# science_controller.net
KiCad netlist of a schematic drawn in EAGLE
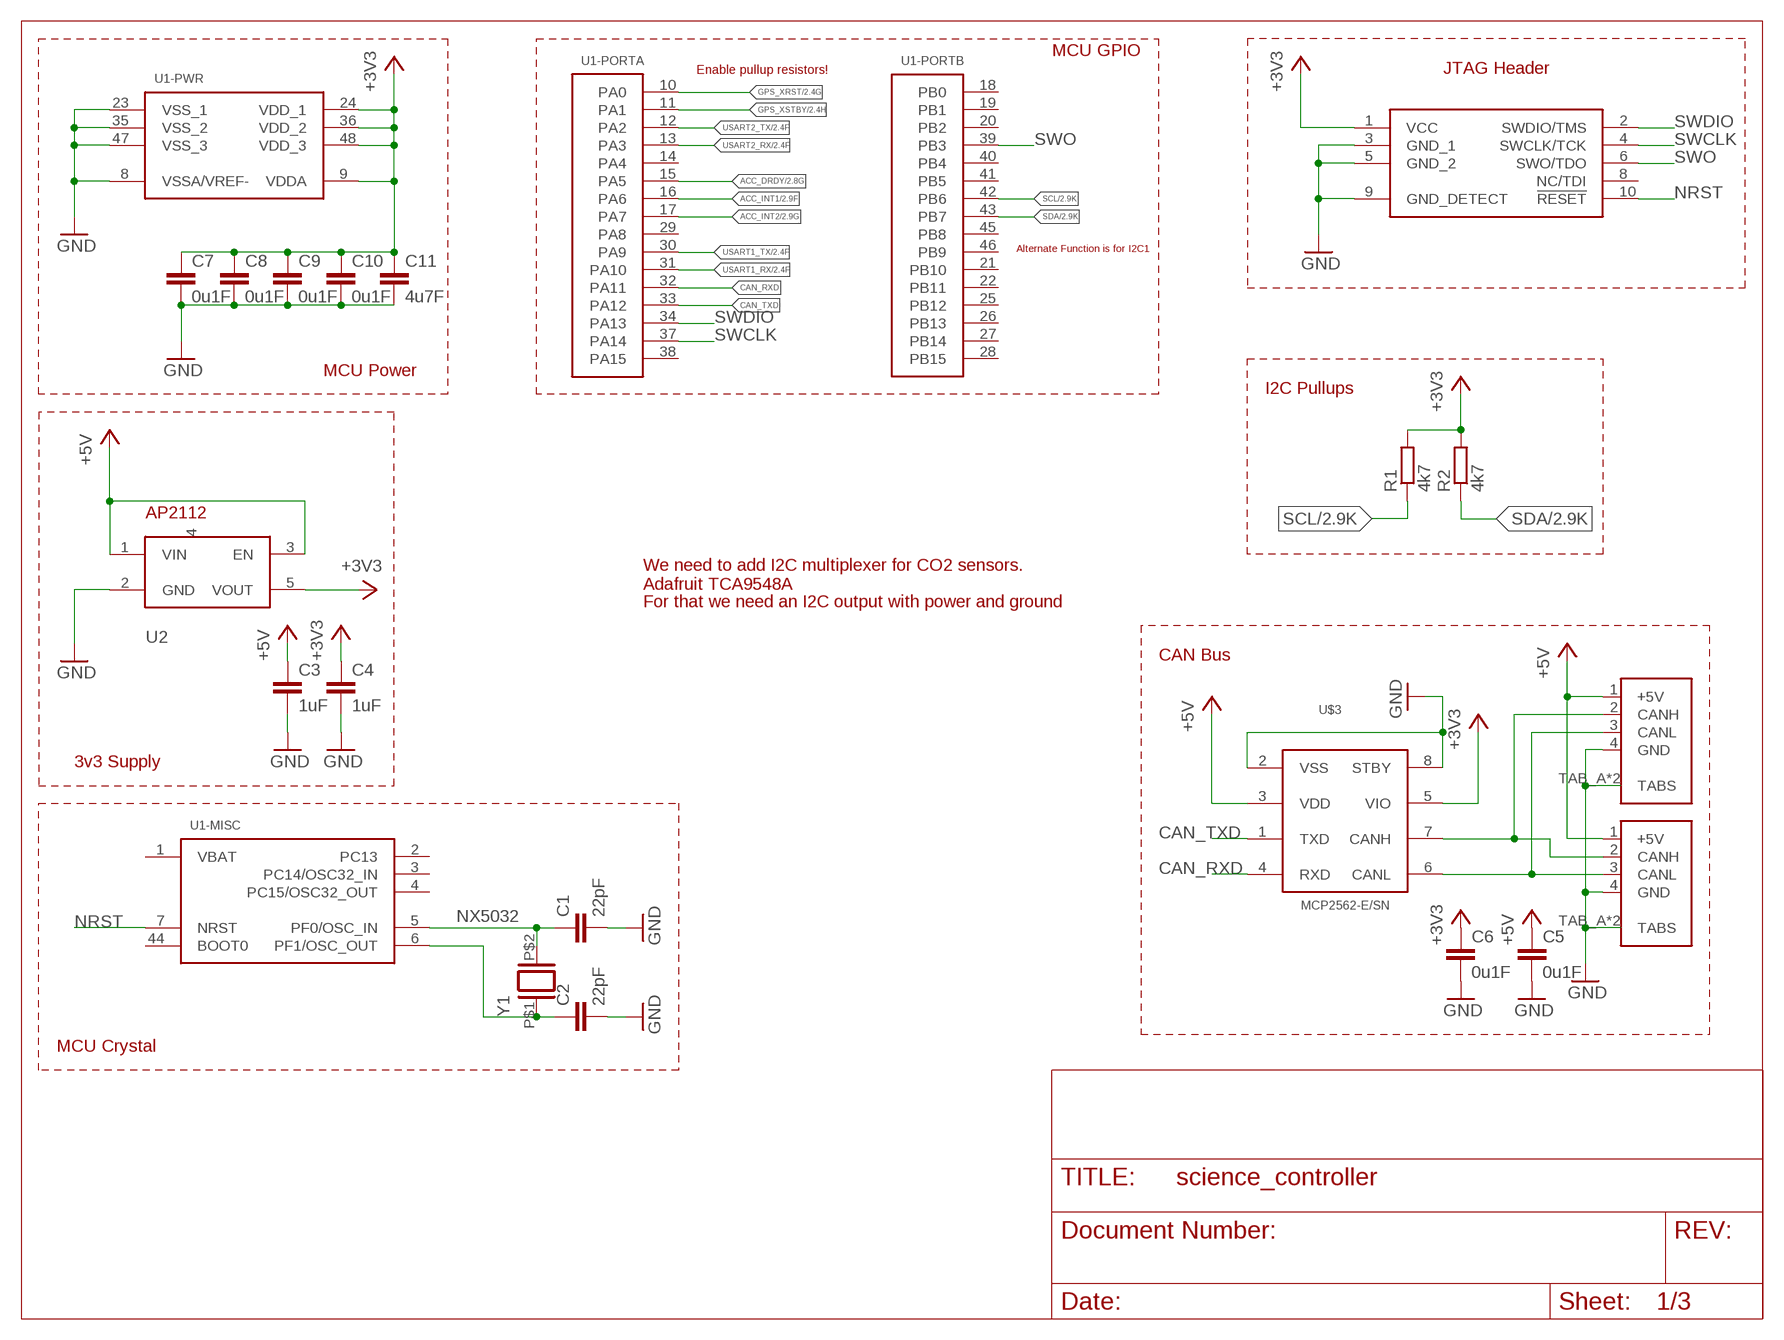
[diagram p0: schematic, sheet 1]
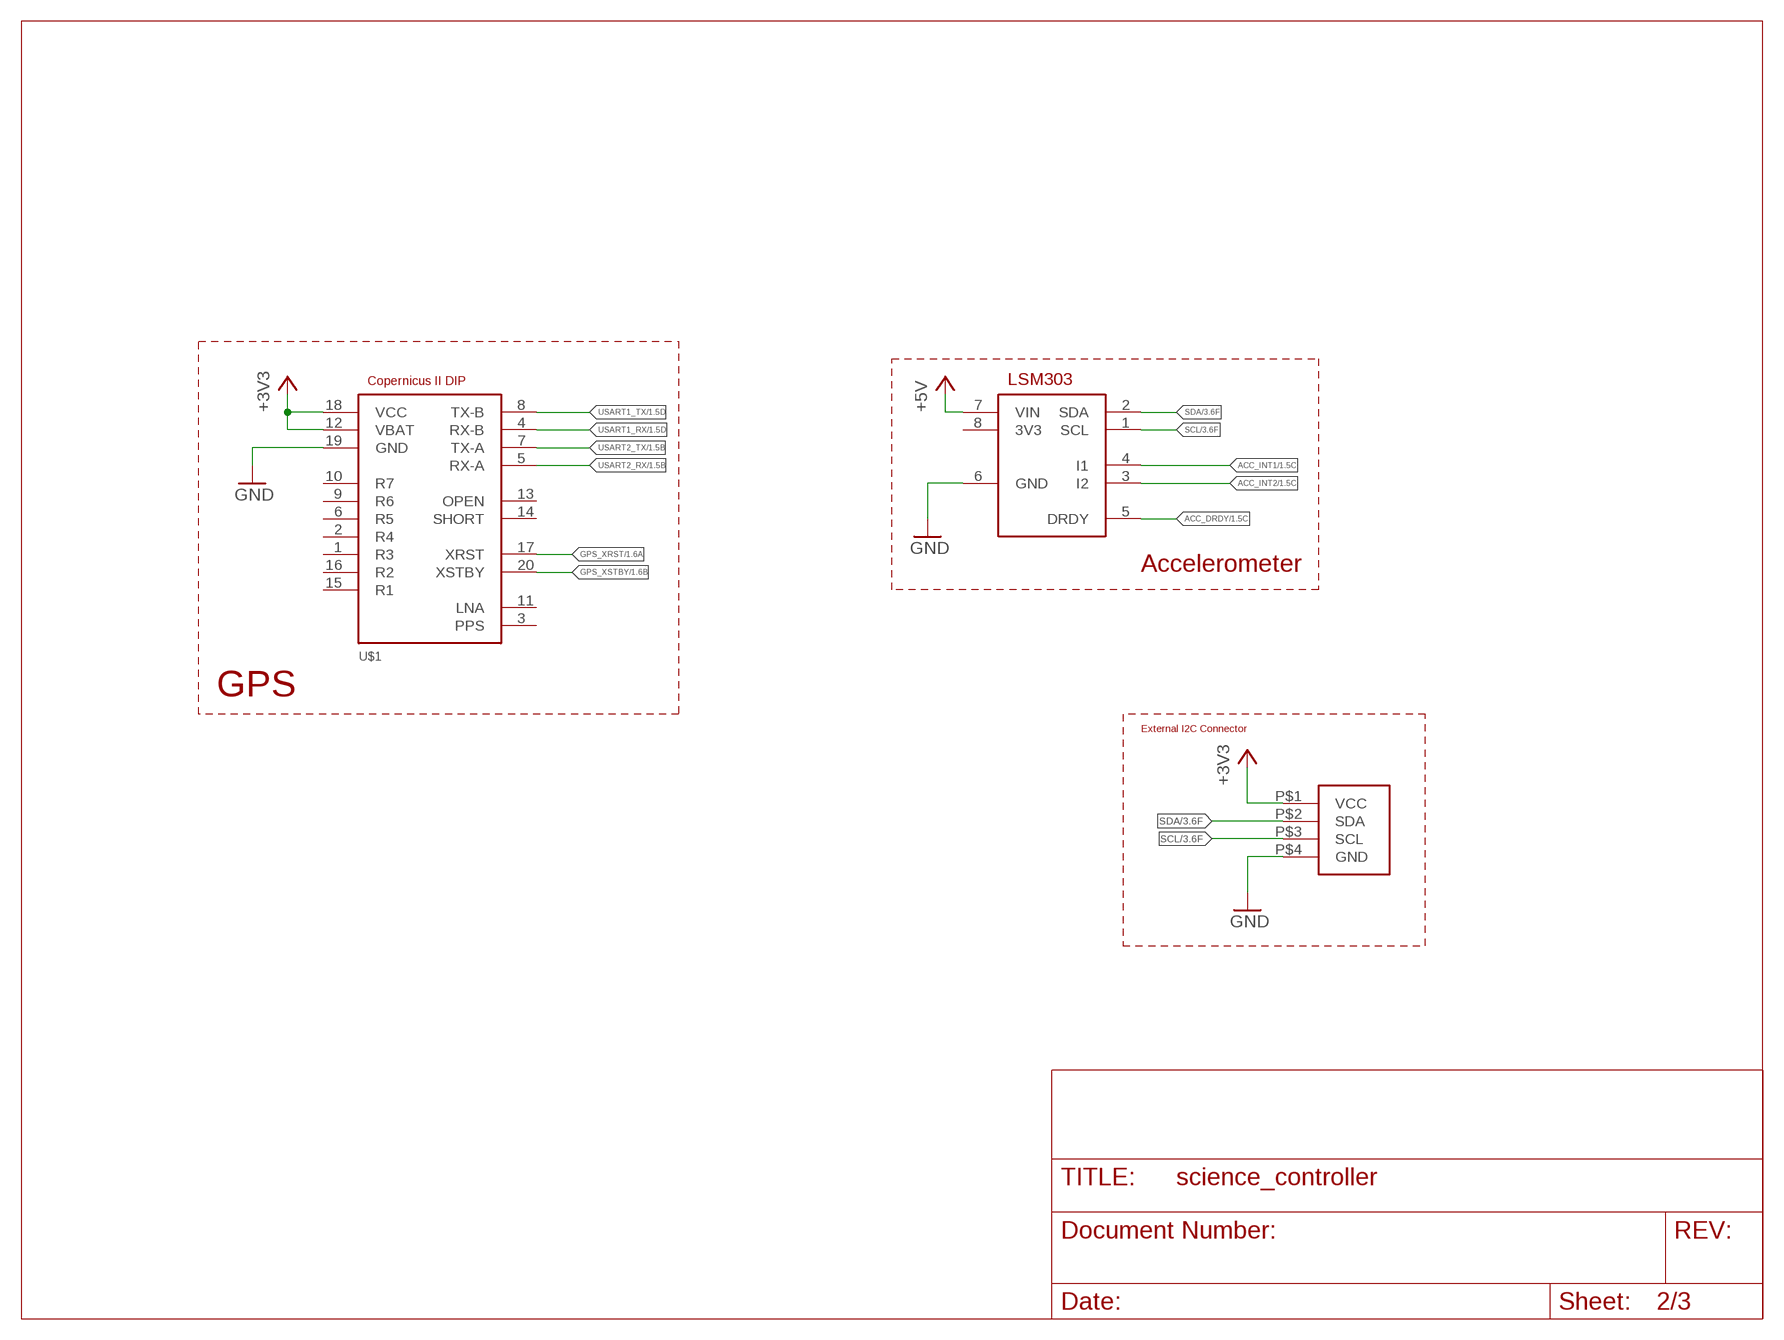
[diagram p1: schematic, sheet 2]
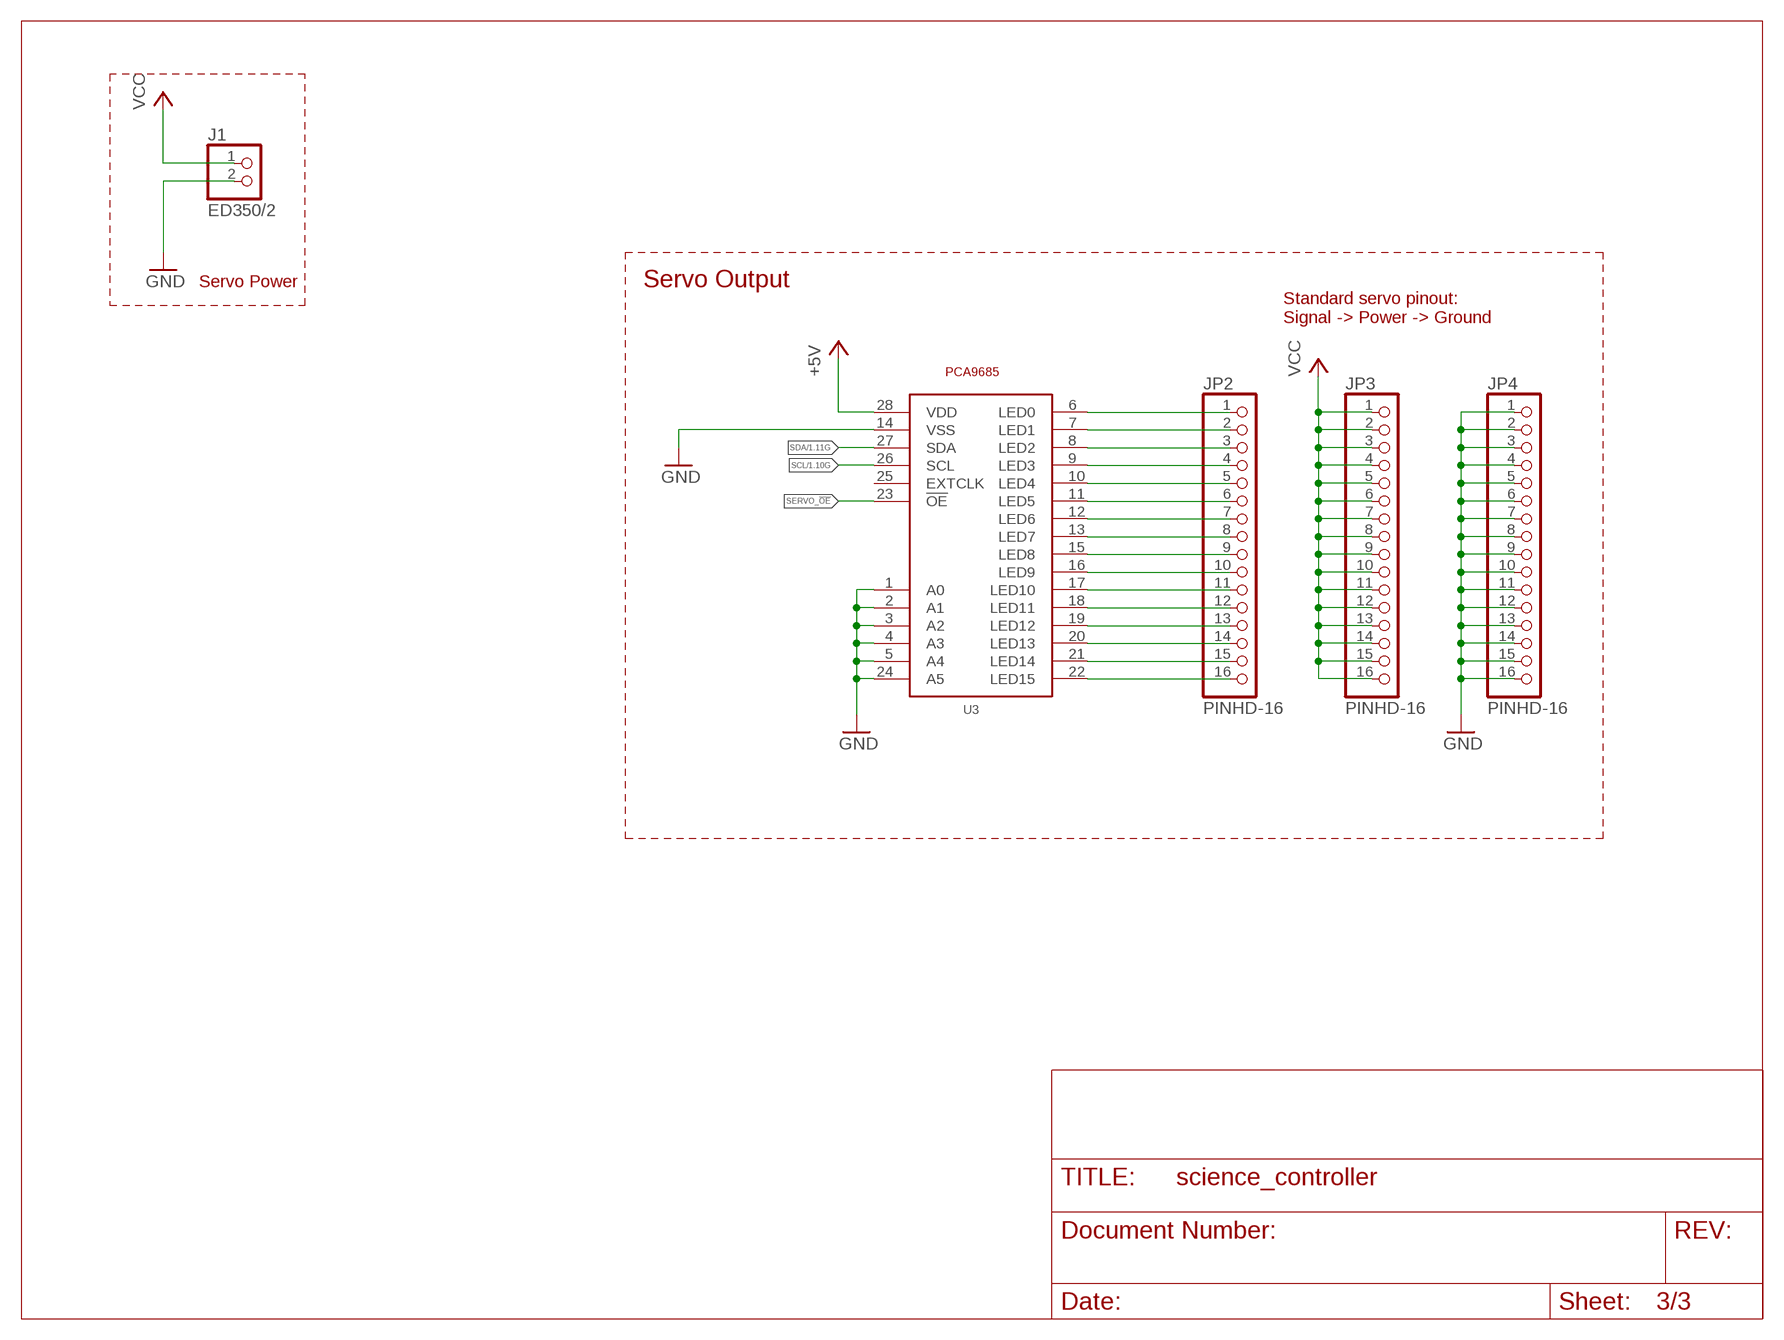
[diagram p2: schematic, sheet 3]

(export (version "E")
  (design (tool "Eeschema 10.0.6"))
  (components
    (comp (ref "C1")
      (value "22pF")
      (footprint "eagle-import:C0805")
      (libsource (lib "eagle-import") (part "C-EUC0805"))
    )
    (comp (ref "C2")
      (value "22pF")
      (footprint "eagle-import:C0805")
      (libsource (lib "eagle-import") (part "C-EUC0805"))
    )
    (comp (ref "C3")
      (value "1uF")
      (footprint "eagle-import:C0805")
      (libsource (lib "eagle-import") (part "C-EUC0805"))
    )
    (comp (ref "C4")
      (value "1uF")
      (footprint "eagle-import:C0805")
      (libsource (lib "eagle-import") (part "C-EUC0805"))
    )
    (comp (ref "C5")
      (value "0u1F")
      (footprint "eagle-import:C0805")
      (libsource (lib "eagle-import") (part "C-EUC0805"))
    )
    (comp (ref "C6")
      (value "0u1F")
      (footprint "eagle-import:C0805")
      (libsource (lib "eagle-import") (part "C-EUC0805"))
    )
    (comp (ref "C7")
      (value "0u1F")
      (footprint "eagle-import:C0805")
      (libsource (lib "eagle-import") (part "C-EUC0805"))
    )
    (comp (ref "C8")
      (value "0u1F")
      (footprint "eagle-import:C0805")
      (libsource (lib "eagle-import") (part "C-EUC0805"))
    )
    (comp (ref "C9")
      (value "0u1F")
      (footprint "eagle-import:C0805")
      (libsource (lib "eagle-import") (part "C-EUC0805"))
    )
    (comp (ref "C10")
      (value "0u1F")
      (footprint "eagle-import:C0805")
      (libsource (lib "eagle-import") (part "C-EUC0805"))
    )
    (comp (ref "C11")
      (value "4u7F")
      (footprint "eagle-import:C0805")
      (libsource (lib "eagle-import") (part "C-EUC0805"))
    )
    (comp (ref "CON1")
      (value "UAVCAN_MICRO")
      (footprint "eagle-import:SM04B-GHS-TB")
      (libsource (lib "eagle-import") (part "UAVCAN_MICRO"))
    )
    (comp (ref "CON2")
      (value "UAVCAN_MICRO")
      (footprint "eagle-import:SM04B-GHS-TB")
      (libsource (lib "eagle-import") (part "UAVCAN_MICRO"))
    )
    (comp (ref "JP1")
      (value "CORTEX-M-DBG")
      (footprint "eagle-import:FTSH-105-01-F-DV-007")
      (libsource (lib "eagle-import") (part "CORTEX-M-DBG"))
    )
    (comp (ref "R1")
      (value "4k7")
      (footprint "eagle-import:R0805")
      (libsource (lib "eagle-import") (part "R-EU_R0805"))
    )
    (comp (ref "R2")
      (value "4k7")
      (footprint "eagle-import:R0805")
      (libsource (lib "eagle-import") (part "R-EU_R0805"))
    )
    (comp (ref "U$3")
      (value "MCP2562-E/SN")
      (footprint "eagle-import:SOIC8")
      (libsource (lib "eagle-import") (part "MCP2562-E/SN"))
    )
    (comp (ref "U1")
      (value "STM32F303CB")
      (footprint "eagle-import:LQFP48")
      (libsource (lib "eagle-import") (part "STM32F303CB"))
    )
    (comp (ref "U2")
      (value "AP2112K-3.3TRG1")
      (footprint "eagle-import:SOT25")
      (libsource (lib "eagle-import") (part "AP2112K-3.3TRG1"))
    )
    (comp (ref "Y1")
      (value "NX5032")
      (footprint "eagle-import:NX5032")
      (libsource (lib "eagle-import") (part "NX5032"))
    )
    (comp (ref "J1")
      (value "ED350/2")
      (footprint "eagle-import:ED350_2")
      (libsource (lib "eagle-import") (part "ED350/2"))
    )
    (comp (ref "JP2")
      (value "PINHD-16")
      (footprint "eagle-import:1X16")
      (libsource (lib "eagle-import") (part "PINHD-16"))
    )
    (comp (ref "JP3")
      (value "PINHD-16")
      (footprint "eagle-import:1X16")
      (libsource (lib "eagle-import") (part "PINHD-16"))
    )
    (comp (ref "JP4")
      (value "PINHD-16")
      (footprint "eagle-import:1X16")
      (libsource (lib "eagle-import") (part "PINHD-16"))
    )
    (comp (ref "U3")
      (value "PCA9685PW")
      (footprint "eagle-import:TSSOP28")
      (libsource (lib "eagle-import") (part "PCA9685PW"))
    )
    (comp (ref "P1")
      (value "I2C-PWR")
      (footprint "eagle-import:TE_5-103669-3")
      (libsource (lib "eagle-import") (part "I2C-PWR"))
    )
    (comp (ref "U$1")
      (value "COPERN2-DIP")
      (footprint "eagle-import:COPERN2-DIP")
      (libsource (lib "eagle-import") (part "COPERN2-DIP"))
    )
    (comp (ref "U$2")
      (value "LSM303-BRKOUT")
      (footprint "eagle-import:1X08")
      (libsource (lib "eagle-import") (part "LSM303-BRKOUT"))
    )
  )
  (nets
    (net (code "1") (name "+3V3") (class "Default")
      (node (ref "C10") (pin "1") (pinfunction "1_1") (pintype "passive"))
      (node (ref "C11") (pin "1") (pinfunction "1_1") (pintype "passive"))
      (node (ref "C4") (pin "1") (pinfunction "1_1") (pintype "passive"))
      (node (ref "C6") (pin "1") (pinfunction "1_1") (pintype "passive"))
      (node (ref "C7") (pin "1") (pinfunction "1_1") (pintype "passive"))
      (node (ref "C8") (pin "1") (pinfunction "1_1") (pintype "passive"))
      (node (ref "C9") (pin "1") (pinfunction "1_1") (pintype "passive"))
      (node (ref "JP1") (pin "1") (pinfunction "VCC_1") (pintype "bidirectional"))
      (node (ref "P1") (pin "P$1") (pinfunction "VCC_P$1") (pintype "bidirectional"))
      (node (ref "R1") (pin "2") (pinfunction "2_2") (pintype "passive"))
      (node (ref "R2") (pin "2") (pinfunction "2_2") (pintype "passive"))
      (node (ref "U$1") (pin "12") (pinfunction "VBAT_12") (pintype "bidirectional"))
      (node (ref "U$1") (pin "18") (pinfunction "VCC_18") (pintype "bidirectional"))
      (node (ref "U$3") (pin "5") (pinfunction "VIO_5") (pintype "bidirectional"))
      (node (ref "U1") (pin "24") (pinfunction "VDD_1_24") (pintype "bidirectional"))
      (node (ref "U1") (pin "36") (pinfunction "VDD_2_36") (pintype "bidirectional"))
      (node (ref "U1") (pin "48") (pinfunction "VDD_3_48") (pintype "bidirectional"))
      (node (ref "U1") (pin "9") (pinfunction "VDDA_9") (pintype "bidirectional"))
      (node (ref "U2") (pin "5") (pinfunction "VOUT_5") (pintype "bidirectional"))
    )
    (net (code "2") (name "+5V") (class "Default")
      (node (ref "C3") (pin "1") (pinfunction "1_1") (pintype "passive"))
      (node (ref "C5") (pin "1") (pinfunction "1_1") (pintype "passive"))
      (node (ref "CON1") (pin "1") (pinfunction "+5V_1") (pintype "bidirectional"))
      (node (ref "CON2") (pin "1") (pinfunction "+5V_1") (pintype "bidirectional"))
      (node (ref "U$2") (pin "7") (pinfunction "VIN_7") (pintype "bidirectional"))
      (node (ref "U$3") (pin "3") (pinfunction "VDD_3") (pintype "bidirectional"))
      (node (ref "U2") (pin "1") (pinfunction "VIN_1") (pintype "bidirectional"))
      (node (ref "U2") (pin "3") (pinfunction "EN_3") (pintype "bidirectional"))
      (node (ref "U3") (pin "28") (pinfunction "VDD_28") (pintype "bidirectional"))
    )
    (net (code "3") (name "ACC_DRDY") (class "Default")
      (node (ref "U$2") (pin "5") (pinfunction "DRDY_5") (pintype "bidirectional"))
      (node (ref "U1") (pin "15") (pinfunction "PA5_15") (pintype "bidirectional"))
    )
    (net (code "4") (name "ACC_INT1") (class "Default")
      (node (ref "U$2") (pin "4") (pinfunction "I1_4") (pintype "bidirectional"))
      (node (ref "U1") (pin "16") (pinfunction "PA6_16") (pintype "bidirectional"))
    )
    (net (code "5") (name "ACC_INT2") (class "Default")
      (node (ref "U$2") (pin "3") (pinfunction "I2_3") (pintype "bidirectional"))
      (node (ref "U1") (pin "17") (pinfunction "PA7_17") (pintype "bidirectional"))
    )
    (net (code "6") (name "CAN_RXD") (class "Default")
      (node (ref "U$3") (pin "4") (pinfunction "RXD_4") (pintype "bidirectional"))
      (node (ref "U1") (pin "32") (pinfunction "PA11_32") (pintype "bidirectional"))
    )
    (net (code "7") (name "CAN_TXD") (class "Default")
      (node (ref "U$3") (pin "1") (pinfunction "TXD_1") (pintype "bidirectional"))
      (node (ref "U1") (pin "33") (pinfunction "PA12_33") (pintype "bidirectional"))
    )
    (net (code "8") (name "GND") (class "Default")
      (node (ref "C1") (pin "2") (pinfunction "2_2") (pintype "passive"))
      (node (ref "C10") (pin "2") (pinfunction "2_2") (pintype "passive"))
      (node (ref "C11") (pin "2") (pinfunction "2_2") (pintype "passive"))
      (node (ref "C2") (pin "2") (pinfunction "2_2") (pintype "passive"))
      (node (ref "C3") (pin "2") (pinfunction "2_2") (pintype "passive"))
      (node (ref "C4") (pin "2") (pinfunction "2_2") (pintype "passive"))
      (node (ref "C5") (pin "2") (pinfunction "2_2") (pintype "passive"))
      (node (ref "C6") (pin "2") (pinfunction "2_2") (pintype "passive"))
      (node (ref "C7") (pin "2") (pinfunction "2_2") (pintype "passive"))
      (node (ref "C8") (pin "2") (pinfunction "2_2") (pintype "passive"))
      (node (ref "C9") (pin "2") (pinfunction "2_2") (pintype "passive"))
      (node (ref "CON1") (pin "4") (pinfunction "GND_4") (pintype "bidirectional"))
      (node (ref "CON1") (pin "TAB_A") (pinfunction "TABS_TAB_A") (pintype "bidirectional"))
      (node (ref "CON1") (pin "TAB_B") (pinfunction "TABS_TAB_B") (pintype "bidirectional"))
      (node (ref "CON2") (pin "4") (pinfunction "GND_4") (pintype "bidirectional"))
      (node (ref "CON2") (pin "TAB_A") (pinfunction "TABS_TAB_A") (pintype "bidirectional"))
      (node (ref "CON2") (pin "TAB_B") (pinfunction "TABS_TAB_B") (pintype "bidirectional"))
      (node (ref "J1") (pin "2") (pinfunction "2_2") (pintype "passive"))
      (node (ref "JP1") (pin "3") (pinfunction "GND_1_3") (pintype "bidirectional"))
      (node (ref "JP1") (pin "5") (pinfunction "GND_2_5") (pintype "bidirectional"))
      (node (ref "JP1") (pin "9") (pinfunction "GND_DETECT_9") (pintype "bidirectional"))
      (node (ref "JP4") (pin "1") (pinfunction "1_1") (pintype "passive"))
      (node (ref "JP4") (pin "10") (pinfunction "10_10") (pintype "passive"))
      (node (ref "JP4") (pin "11") (pinfunction "11_11") (pintype "passive"))
      (node (ref "JP4") (pin "12") (pinfunction "12_12") (pintype "passive"))
      (node (ref "JP4") (pin "13") (pinfunction "13_13") (pintype "passive"))
      (node (ref "JP4") (pin "14") (pinfunction "14_14") (pintype "passive"))
      (node (ref "JP4") (pin "15") (pinfunction "15_15") (pintype "passive"))
      (node (ref "JP4") (pin "16") (pinfunction "16_16") (pintype "passive"))
      (node (ref "JP4") (pin "2") (pinfunction "2_2") (pintype "passive"))
      (node (ref "JP4") (pin "3") (pinfunction "3_3") (pintype "passive"))
      (node (ref "JP4") (pin "4") (pinfunction "4_4") (pintype "passive"))
      (node (ref "JP4") (pin "5") (pinfunction "5_5") (pintype "passive"))
      (node (ref "JP4") (pin "6") (pinfunction "6_6") (pintype "passive"))
      (node (ref "JP4") (pin "7") (pinfunction "7_7") (pintype "passive"))
      (node (ref "JP4") (pin "8") (pinfunction "8_8") (pintype "passive"))
      (node (ref "JP4") (pin "9") (pinfunction "9_9") (pintype "passive"))
      (node (ref "P1") (pin "P$4") (pinfunction "GND_P$4") (pintype "bidirectional"))
      (node (ref "U$1") (pin "19") (pinfunction "GND_19") (pintype "bidirectional"))
      (node (ref "U$2") (pin "6") (pinfunction "GND_6") (pintype "bidirectional"))
      (node (ref "U$3") (pin "2") (pinfunction "VSS_2") (pintype "bidirectional"))
      (node (ref "U$3") (pin "8") (pinfunction "STBY_8") (pintype "bidirectional"))
      (node (ref "U1") (pin "23") (pinfunction "VSS_1_23") (pintype "bidirectional"))
      (node (ref "U1") (pin "35") (pinfunction "VSS_2_35") (pintype "bidirectional"))
      (node (ref "U1") (pin "47") (pinfunction "VSS_3_47") (pintype "bidirectional"))
      (node (ref "U1") (pin "8") (pinfunction "VSSA/VREF-_8") (pintype "bidirectional"))
      (node (ref "U2") (pin "2") (pinfunction "GND_2") (pintype "bidirectional"))
      (node (ref "U3") (pin "1") (pinfunction "A0_1") (pintype "bidirectional"))
      (node (ref "U3") (pin "14") (pinfunction "VSS_14") (pintype "bidirectional"))
      (node (ref "U3") (pin "2") (pinfunction "A1_2") (pintype "bidirectional"))
      (node (ref "U3") (pin "24") (pinfunction "A5_24") (pintype "bidirectional"))
      (node (ref "U3") (pin "3") (pinfunction "A2_3") (pintype "bidirectional"))
      (node (ref "U3") (pin "4") (pinfunction "A3_4") (pintype "bidirectional"))
      (node (ref "U3") (pin "5") (pinfunction "A4_5") (pintype "bidirectional"))
    )
    (net (code "9") (name "GPS_XRST") (class "Default")
      (node (ref "U$1") (pin "17") (pinfunction "XRST_17") (pintype "bidirectional"))
      (node (ref "U1") (pin "10") (pinfunction "PA0_10") (pintype "bidirectional"))
    )
    (net (code "10") (name "GPS_XSTBY") (class "Default")
      (node (ref "U$1") (pin "20") (pinfunction "XSTBY_20") (pintype "bidirectional"))
      (node (ref "U1") (pin "11") (pinfunction "PA1_11") (pintype "bidirectional"))
    )
    (net (code "11") (name "NRST") (class "Default")
      (node (ref "JP1") (pin "10") (pinfunction "~{RESET}_10") (pintype "bidirectional"))
      (node (ref "U1") (pin "7") (pinfunction "NRST_7") (pintype "bidirectional"))
    )
    (net (code "12") (name "Net-(CON1-CANH)") (class "Default")
      (node (ref "CON1") (pin "2") (pinfunction "CANH_2") (pintype "bidirectional"))
      (node (ref "CON2") (pin "2") (pinfunction "CANH_2") (pintype "bidirectional"))
      (node (ref "U$3") (pin "7") (pinfunction "CANH_7") (pintype "bidirectional"))
    )
    (net (code "13") (name "Net-(CON1-CANL)") (class "Default")
      (node (ref "CON1") (pin "3") (pinfunction "CANL_3") (pintype "bidirectional"))
      (node (ref "CON2") (pin "3") (pinfunction "CANL_3") (pintype "bidirectional"))
      (node (ref "U$3") (pin "6") (pinfunction "CANL_6") (pintype "bidirectional"))
    )
    (net (code "14") (name "Net-(U1A-PF0{slash}OSC_IN)") (class "Default")
      (node (ref "C1") (pin "1") (pinfunction "1_1") (pintype "passive"))
      (node (ref "U1") (pin "5") (pinfunction "PF0/OSC_IN_5") (pintype "bidirectional"))
      (node (ref "Y1") (pin "P$2") (pinfunction "2_P$2") (pintype "passive"))
    )
    (net (code "15") (name "Net-(U1A-PF1{slash}OSC_OUT)") (class "Default")
      (node (ref "C2") (pin "1") (pinfunction "1_1") (pintype "passive"))
      (node (ref "U1") (pin "6") (pinfunction "PF1/OSC_OUT_6") (pintype "bidirectional"))
      (node (ref "Y1") (pin "P$1") (pinfunction "1_P$1") (pintype "passive"))
    )
    (net (code "16") (name "Net-(U3-LED0)") (class "Default")
      (node (ref "JP2") (pin "1") (pinfunction "1_1") (pintype "passive"))
      (node (ref "U3") (pin "6") (pinfunction "LED0_6") (pintype "bidirectional"))
    )
    (net (code "17") (name "Net-(U3-LED1)") (class "Default")
      (node (ref "JP2") (pin "2") (pinfunction "2_2") (pintype "passive"))
      (node (ref "U3") (pin "7") (pinfunction "LED1_7") (pintype "bidirectional"))
    )
    (net (code "18") (name "Net-(U3-LED2)") (class "Default")
      (node (ref "JP2") (pin "3") (pinfunction "3_3") (pintype "passive"))
      (node (ref "U3") (pin "8") (pinfunction "LED2_8") (pintype "bidirectional"))
    )
    (net (code "19") (name "Net-(U3-LED3)") (class "Default")
      (node (ref "JP2") (pin "4") (pinfunction "4_4") (pintype "passive"))
      (node (ref "U3") (pin "9") (pinfunction "LED3_9") (pintype "bidirectional"))
    )
    (net (code "20") (name "Net-(U3-LED4)") (class "Default")
      (node (ref "JP2") (pin "5") (pinfunction "5_5") (pintype "passive"))
      (node (ref "U3") (pin "10") (pinfunction "LED4_10") (pintype "bidirectional"))
    )
    (net (code "21") (name "Net-(U3-LED5)") (class "Default")
      (node (ref "JP2") (pin "6") (pinfunction "6_6") (pintype "passive"))
      (node (ref "U3") (pin "11") (pinfunction "LED5_11") (pintype "bidirectional"))
    )
    (net (code "22") (name "Net-(U3-LED6)") (class "Default")
      (node (ref "JP2") (pin "7") (pinfunction "7_7") (pintype "passive"))
      (node (ref "U3") (pin "12") (pinfunction "LED6_12") (pintype "bidirectional"))
    )
    (net (code "23") (name "Net-(U3-LED7)") (class "Default")
      (node (ref "JP2") (pin "8") (pinfunction "8_8") (pintype "passive"))
      (node (ref "U3") (pin "13") (pinfunction "LED7_13") (pintype "bidirectional"))
    )
    (net (code "24") (name "Net-(U3-LED8)") (class "Default")
      (node (ref "JP2") (pin "9") (pinfunction "9_9") (pintype "passive"))
      (node (ref "U3") (pin "15") (pinfunction "LED8_15") (pintype "bidirectional"))
    )
    (net (code "25") (name "Net-(U3-LED9)") (class "Default")
      (node (ref "JP2") (pin "10") (pinfunction "10_10") (pintype "passive"))
      (node (ref "U3") (pin "16") (pinfunction "LED9_16") (pintype "bidirectional"))
    )
    (net (code "26") (name "Net-(U3-LED10)") (class "Default")
      (node (ref "JP2") (pin "11") (pinfunction "11_11") (pintype "passive"))
      (node (ref "U3") (pin "17") (pinfunction "LED10_17") (pintype "bidirectional"))
    )
    (net (code "27") (name "Net-(U3-LED11)") (class "Default")
      (node (ref "JP2") (pin "12") (pinfunction "12_12") (pintype "passive"))
      (node (ref "U3") (pin "18") (pinfunction "LED11_18") (pintype "bidirectional"))
    )
    (net (code "28") (name "Net-(U3-LED12)") (class "Default")
      (node (ref "JP2") (pin "13") (pinfunction "13_13") (pintype "passive"))
      (node (ref "U3") (pin "19") (pinfunction "LED12_19") (pintype "bidirectional"))
    )
    (net (code "29") (name "Net-(U3-LED13)") (class "Default")
      (node (ref "JP2") (pin "14") (pinfunction "14_14") (pintype "passive"))
      (node (ref "U3") (pin "20") (pinfunction "LED13_20") (pintype "bidirectional"))
    )
    (net (code "30") (name "Net-(U3-LED14)") (class "Default")
      (node (ref "JP2") (pin "15") (pinfunction "15_15") (pintype "passive"))
      (node (ref "U3") (pin "21") (pinfunction "LED14_21") (pintype "bidirectional"))
    )
    (net (code "31") (name "Net-(U3-LED15)") (class "Default")
      (node (ref "JP2") (pin "16") (pinfunction "16_16") (pintype "passive"))
      (node (ref "U3") (pin "22") (pinfunction "LED15_22") (pintype "bidirectional"))
    )
    (net (code "32") (name "SCL") (class "Default")
      (node (ref "P1") (pin "P$3") (pinfunction "SCL_P$3") (pintype "bidirectional"))
      (node (ref "R1") (pin "1") (pinfunction "1_1") (pintype "passive"))
      (node (ref "U$2") (pin "1") (pinfunction "SCL_1") (pintype "bidirectional"))
      (node (ref "U1") (pin "42") (pinfunction "PB6_42") (pintype "bidirectional"))
      (node (ref "U3") (pin "26") (pinfunction "SCL_26") (pintype "bidirectional"))
    )
    (net (code "33") (name "SDA") (class "Default")
      (node (ref "P1") (pin "P$2") (pinfunction "SDA_P$2") (pintype "bidirectional"))
      (node (ref "R2") (pin "1") (pinfunction "1_1") (pintype "passive"))
      (node (ref "U$2") (pin "2") (pinfunction "SDA_2") (pintype "bidirectional"))
      (node (ref "U1") (pin "43") (pinfunction "PB7_43") (pintype "bidirectional"))
      (node (ref "U3") (pin "27") (pinfunction "SDA_27") (pintype "bidirectional"))
    )
    (net (code "34") (name "SERVO_~{OE}") (class "Default")
      (node (ref "U3") (pin "23") (pinfunction "~{OE}_23") (pintype "bidirectional"))
    )
    (net (code "35") (name "SWCLK") (class "Default")
      (node (ref "JP1") (pin "4") (pinfunction "SWCLK/TCK_4") (pintype "bidirectional"))
      (node (ref "U1") (pin "37") (pinfunction "PA14_37") (pintype "bidirectional"))
    )
    (net (code "36") (name "SWDIO") (class "Default")
      (node (ref "JP1") (pin "2") (pinfunction "SWDIO/TMS_2") (pintype "bidirectional"))
      (node (ref "U1") (pin "34") (pinfunction "PA13_34") (pintype "bidirectional"))
    )
    (net (code "37") (name "SWO") (class "Default")
      (node (ref "JP1") (pin "6") (pinfunction "SWO/TDO_6") (pintype "bidirectional"))
      (node (ref "U1") (pin "39") (pinfunction "PB3_39") (pintype "bidirectional"))
    )
    (net (code "38") (name "USART1_RX") (class "Default")
      (node (ref "U$1") (pin "4") (pinfunction "RX-B_4") (pintype "bidirectional"))
      (node (ref "U1") (pin "31") (pinfunction "PA10_31") (pintype "bidirectional"))
    )
    (net (code "39") (name "USART1_TX") (class "Default")
      (node (ref "U$1") (pin "8") (pinfunction "TX-B_8") (pintype "bidirectional"))
      (node (ref "U1") (pin "30") (pinfunction "PA9_30") (pintype "bidirectional"))
    )
    (net (code "40") (name "USART2_RX") (class "Default")
      (node (ref "U$1") (pin "5") (pinfunction "RX-A_5") (pintype "bidirectional"))
      (node (ref "U1") (pin "13") (pinfunction "PA3_13") (pintype "bidirectional"))
    )
    (net (code "41") (name "USART2_TX") (class "Default")
      (node (ref "U$1") (pin "7") (pinfunction "TX-A_7") (pintype "bidirectional"))
      (node (ref "U1") (pin "12") (pinfunction "PA2_12") (pintype "bidirectional"))
    )
    (net (code "42") (name "VCC") (class "Default")
      (node (ref "J1") (pin "1") (pinfunction "1_1") (pintype "passive"))
      (node (ref "JP3") (pin "1") (pinfunction "1_1") (pintype "passive"))
      (node (ref "JP3") (pin "10") (pinfunction "10_10") (pintype "passive"))
      (node (ref "JP3") (pin "11") (pinfunction "11_11") (pintype "passive"))
      (node (ref "JP3") (pin "12") (pinfunction "12_12") (pintype "passive"))
      (node (ref "JP3") (pin "13") (pinfunction "13_13") (pintype "passive"))
      (node (ref "JP3") (pin "14") (pinfunction "14_14") (pintype "passive"))
      (node (ref "JP3") (pin "15") (pinfunction "15_15") (pintype "passive"))
      (node (ref "JP3") (pin "16") (pinfunction "16_16") (pintype "passive"))
      (node (ref "JP3") (pin "2") (pinfunction "2_2") (pintype "passive"))
      (node (ref "JP3") (pin "3") (pinfunction "3_3") (pintype "passive"))
      (node (ref "JP3") (pin "4") (pinfunction "4_4") (pintype "passive"))
      (node (ref "JP3") (pin "5") (pinfunction "5_5") (pintype "passive"))
      (node (ref "JP3") (pin "6") (pinfunction "6_6") (pintype "passive"))
      (node (ref "JP3") (pin "7") (pinfunction "7_7") (pintype "passive"))
      (node (ref "JP3") (pin "8") (pinfunction "8_8") (pintype "passive"))
      (node (ref "JP3") (pin "9") (pinfunction "9_9") (pintype "passive"))
    )
    (net (code "43") (name "unconnected-(JP1-NC{slash}TDI-Pad8)") (class "Default")
      (node (ref "JP1") (pin "8") (pinfunction "NC/TDI_8") (pintype "bidirectional"))
    )
    (net (code "44") (name "unconnected-(U$1-LNA-Pad11)") (class "Default")
      (node (ref "U$1") (pin "11") (pinfunction "LNA_11") (pintype "bidirectional"))
    )
    (net (code "45") (name "unconnected-(U$1-OPEN-Pad13)") (class "Default")
      (node (ref "U$1") (pin "13") (pinfunction "OPEN_13") (pintype "bidirectional"))
    )
    (net (code "46") (name "unconnected-(U$1-PPS-Pad3)") (class "Default")
      (node (ref "U$1") (pin "3") (pinfunction "PPS_3") (pintype "bidirectional"))
    )
    (net (code "47") (name "unconnected-(U$1-R1-Pad15)") (class "Default")
      (node (ref "U$1") (pin "15") (pinfunction "R1_15") (pintype "bidirectional"))
    )
    (net (code "48") (name "unconnected-(U$1-R2-Pad16)") (class "Default")
      (node (ref "U$1") (pin "16") (pinfunction "R2_16") (pintype "bidirectional"))
    )
    (net (code "49") (name "unconnected-(U$1-R3-Pad1)") (class "Default")
      (node (ref "U$1") (pin "1") (pinfunction "R3_1") (pintype "bidirectional"))
    )
    (net (code "50") (name "unconnected-(U$1-R4-Pad2)") (class "Default")
      (node (ref "U$1") (pin "2") (pinfunction "R4_2") (pintype "bidirectional"))
    )
    (net (code "51") (name "unconnected-(U$1-R5-Pad6)") (class "Default")
      (node (ref "U$1") (pin "6") (pinfunction "R5_6") (pintype "bidirectional"))
    )
    (net (code "52") (name "unconnected-(U$1-R6-Pad9)") (class "Default")
      (node (ref "U$1") (pin "9") (pinfunction "R6_9") (pintype "bidirectional"))
    )
    (net (code "53") (name "unconnected-(U$1-R7-Pad10)") (class "Default")
      (node (ref "U$1") (pin "10") (pinfunction "R7_10") (pintype "bidirectional"))
    )
    (net (code "54") (name "unconnected-(U$1-SHORT-Pad14)") (class "Default")
      (node (ref "U$1") (pin "14") (pinfunction "SHORT_14") (pintype "bidirectional"))
    )
    (net (code "55") (name "unconnected-(U$2-3V3-Pad8)") (class "Default")
      (node (ref "U$2") (pin "8") (pinfunction "3V3_8") (pintype "bidirectional"))
    )
    (net (code "56") (name "unconnected-(U1A-BOOT0-Pad44)") (class "Default")
      (node (ref "U1") (pin "44") (pinfunction "BOOT0_44") (pintype "bidirectional"))
    )
    (net (code "57") (name "unconnected-(U1A-PC13-Pad2)") (class "Default")
      (node (ref "U1") (pin "2") (pinfunction "PC13_2") (pintype "bidirectional"))
    )
    (net (code "58") (name "unconnected-(U1A-PC14{slash}OSC32_IN-Pad3)") (class "Default")
      (node (ref "U1") (pin "3") (pinfunction "PC14/OSC32_IN_3") (pintype "bidirectional"))
    )
    (net (code "59") (name "unconnected-(U1A-PC15{slash}OSC32_OUT-Pad4)") (class "Default")
      (node (ref "U1") (pin "4") (pinfunction "PC15/OSC32_OUT_4") (pintype "bidirectional"))
    )
    (net (code "60") (name "unconnected-(U1A-VBAT-Pad1)") (class "Default")
      (node (ref "U1") (pin "1") (pinfunction "VBAT_1") (pintype "bidirectional"))
    )
    (net (code "61") (name "unconnected-(U1B-PA4-Pad14)") (class "Default")
      (node (ref "U1") (pin "14") (pinfunction "PA4_14") (pintype "bidirectional"))
    )
    (net (code "62") (name "unconnected-(U1B-PA8-Pad29)") (class "Default")
      (node (ref "U1") (pin "29") (pinfunction "PA8_29") (pintype "bidirectional"))
    )
    (net (code "63") (name "unconnected-(U1B-PA15-Pad38)") (class "Default")
      (node (ref "U1") (pin "38") (pinfunction "PA15_38") (pintype "bidirectional"))
    )
    (net (code "64") (name "unconnected-(U1C-PB0-Pad18)") (class "Default")
      (node (ref "U1") (pin "18") (pinfunction "PB0_18") (pintype "bidirectional"))
    )
    (net (code "65") (name "unconnected-(U1C-PB1-Pad19)") (class "Default")
      (node (ref "U1") (pin "19") (pinfunction "PB1_19") (pintype "bidirectional"))
    )
    (net (code "66") (name "unconnected-(U1C-PB2-Pad20)") (class "Default")
      (node (ref "U1") (pin "20") (pinfunction "PB2_20") (pintype "bidirectional"))
    )
    (net (code "67") (name "unconnected-(U1C-PB4-Pad40)") (class "Default")
      (node (ref "U1") (pin "40") (pinfunction "PB4_40") (pintype "bidirectional"))
    )
    (net (code "68") (name "unconnected-(U1C-PB5-Pad41)") (class "Default")
      (node (ref "U1") (pin "41") (pinfunction "PB5_41") (pintype "bidirectional"))
    )
    (net (code "69") (name "unconnected-(U1C-PB8-Pad45)") (class "Default")
      (node (ref "U1") (pin "45") (pinfunction "PB8_45") (pintype "bidirectional"))
    )
    (net (code "70") (name "unconnected-(U1C-PB9-Pad46)") (class "Default")
      (node (ref "U1") (pin "46") (pinfunction "PB9_46") (pintype "bidirectional"))
    )
    (net (code "71") (name "unconnected-(U1C-PB10-Pad21)") (class "Default")
      (node (ref "U1") (pin "21") (pinfunction "PB10_21") (pintype "bidirectional"))
    )
    (net (code "72") (name "unconnected-(U1C-PB11-Pad22)") (class "Default")
      (node (ref "U1") (pin "22") (pinfunction "PB11_22") (pintype "bidirectional"))
    )
    (net (code "73") (name "unconnected-(U1C-PB12-Pad25)") (class "Default")
      (node (ref "U1") (pin "25") (pinfunction "PB12_25") (pintype "bidirectional"))
    )
    (net (code "74") (name "unconnected-(U1C-PB13-Pad26)") (class "Default")
      (node (ref "U1") (pin "26") (pinfunction "PB13_26") (pintype "bidirectional"))
    )
    (net (code "75") (name "unconnected-(U1C-PB14-Pad27)") (class "Default")
      (node (ref "U1") (pin "27") (pinfunction "PB14_27") (pintype "bidirectional"))
    )
    (net (code "76") (name "unconnected-(U1C-PB15-Pad28)") (class "Default")
      (node (ref "U1") (pin "28") (pinfunction "PB15_28") (pintype "bidirectional"))
    )
    (net (code "77") (name "unconnected-(U2-NC-Pad4)") (class "Default")
      (node (ref "U2") (pin "4") (pinfunction "NC_4") (pintype "bidirectional"))
    )
    (net (code "78") (name "unconnected-(U3-EXTCLK-Pad25)") (class "Default")
      (node (ref "U3") (pin "25") (pinfunction "EXTCLK_25") (pintype "bidirectional"))
    )
  )
)
